# tRexRunnerNano.net
KiCad netlist of a schematic drawn in EAGLE
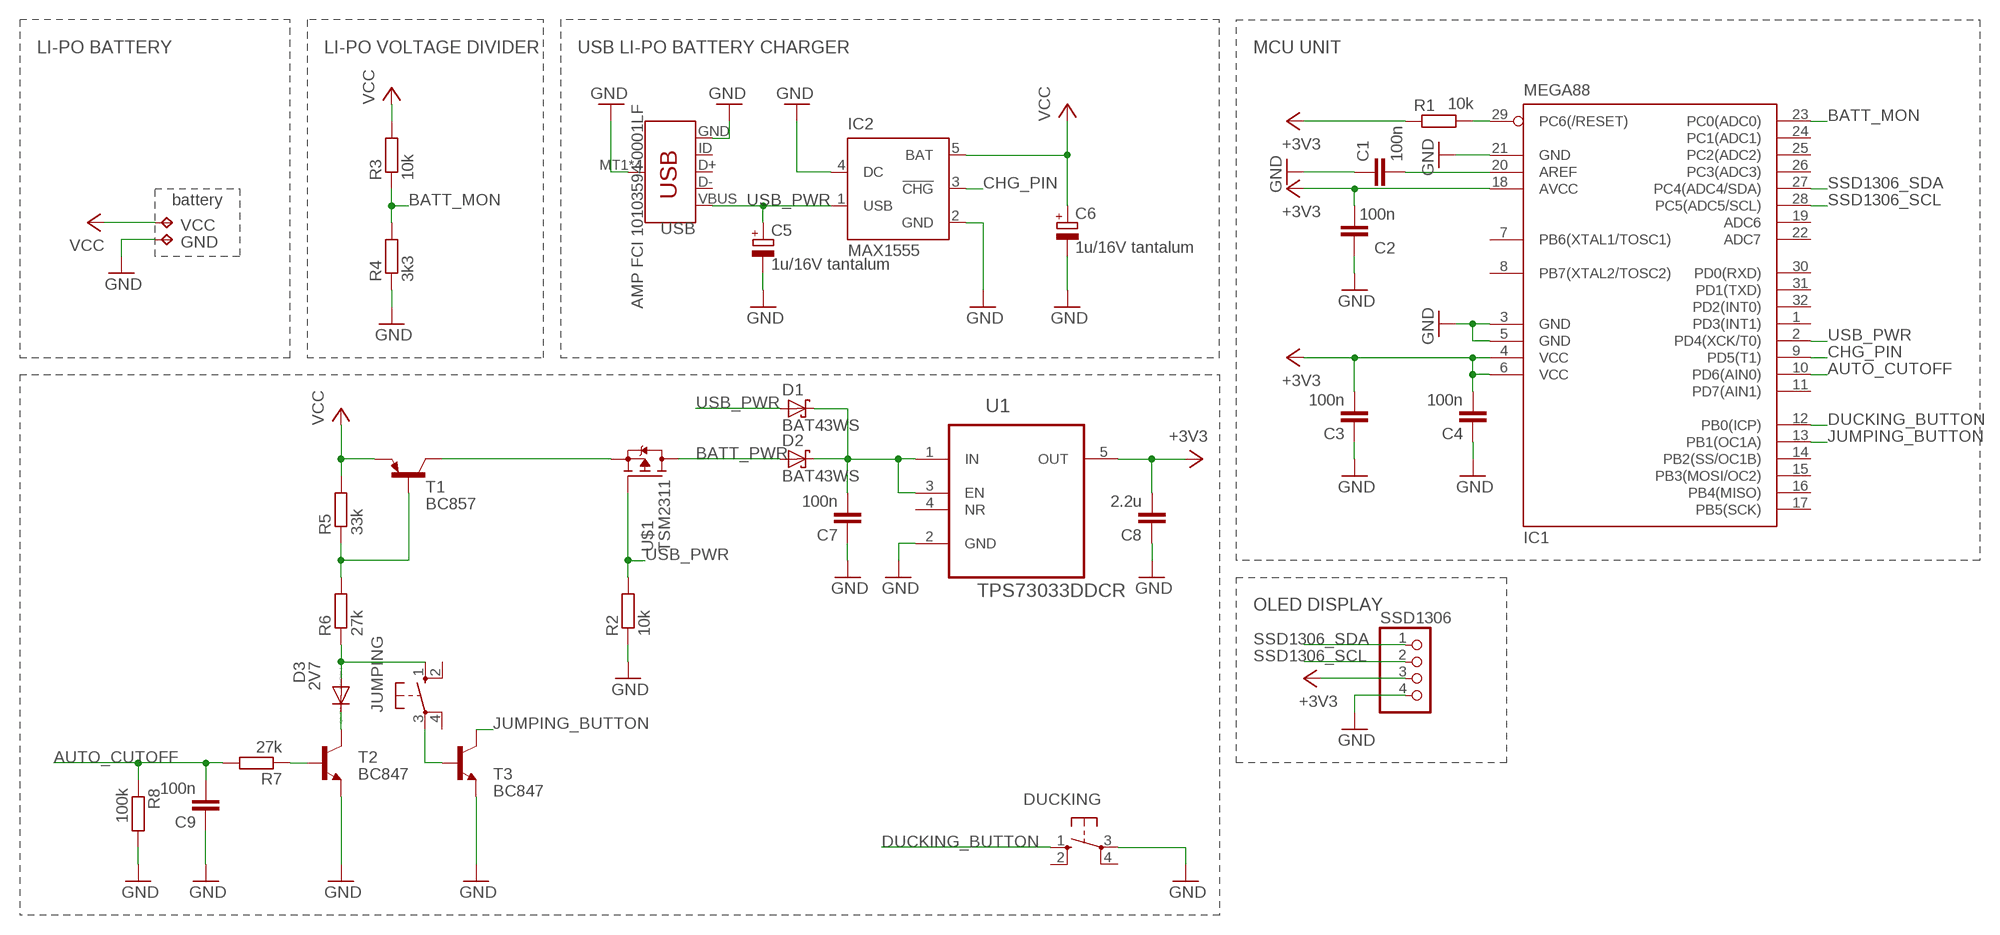
[diagram p0: schematic, sheet 1]

(export (version "E")
  (design (tool "Eeschema 10.0.6"))
  (components
    (comp (ref "C1")
      (value "100n")
      (footprint "eagle-import:C0805")
      (libsource (lib "eagle-import") (part "C-EUC0805"))
    )
    (comp (ref "C2")
      (value "100n")
      (footprint "eagle-import:C0805")
      (libsource (lib "eagle-import") (part "C-EUC0805"))
    )
    (comp (ref "C3")
      (value "100n")
      (footprint "eagle-import:C0805")
      (libsource (lib "eagle-import") (part "C-EUC0805"))
    )
    (comp (ref "C4")
      (value "100n")
      (footprint "eagle-import:C0805")
      (libsource (lib "eagle-import") (part "C-EUC0805"))
    )
    (comp (ref "C5")
      (value "1u/16V tantalum")
      (footprint "eagle-import:SMC_A")
      (libsource (lib "eagle-import") (part "CPOL-EUSMCA"))
    )
    (comp (ref "C6")
      (value "1u/16V tantalum")
      (footprint "eagle-import:SMC_A")
      (libsource (lib "eagle-import") (part "CPOL-EUSMCA"))
    )
    (comp (ref "C7")
      (value "100n")
      (footprint "eagle-import:C0805")
      (libsource (lib "eagle-import") (part "C-EUC0805"))
    )
    (comp (ref "C8")
      (value "2.2u")
      (footprint "eagle-import:C0805")
      (libsource (lib "eagle-import") (part "C-EUC0805"))
    )
    (comp (ref "C9")
      (value "100n")
      (footprint "eagle-import:C0805")
      (libsource (lib "eagle-import") (part "C-EUC0805"))
    )
    (comp (ref "D1")
      (value "BAT43WS")
      (footprint "eagle-import:SOD323_ST")
      (libsource (lib "eagle-import") (part "BAT60J"))
    )
    (comp (ref "D2")
      (value "BAT43WS")
      (footprint "eagle-import:SOD323_ST")
      (libsource (lib "eagle-import") (part "BAT60J"))
    )
    (comp (ref "D3")
      (value "2V7")
      (footprint "eagle-import:SOD80C")
      (libsource (lib "eagle-import") (part "DIODE-SOD80C"))
    )
    (comp (ref "DUCKING")
      (value "10-XX")
      (footprint "eagle-import:B3F-10XX")
      (fields (field (name "MPN") "B3F-1000"))
      (libsource (lib "eagle-import") (part "10-XX"))
    )
    (comp (ref "GND")
      (value "TPTP12R")
      (footprint "eagle-import:TP12R")
      (libsource (lib "eagle-import") (part "TPTP12R"))
    )
    (comp (ref "IC1")
      (value "MEGA88")
      (footprint "eagle-import:TQFP32-08")
      (fields (field (name "MPN") "ATMEGA8-16AU"))
      (libsource (lib "eagle-import") (part "MEGA8-AI"))
    )
    (comp (ref "IC2")
      (value "MAX1555")
      (footprint "eagle-import:SOT23-5L")
      (fields (field (name "MF") "MAXIM") (field (name "MPN") "MAX1555EZK+T"))
      (libsource (lib "eagle-import") (part "MAX1555"))
    )
    (comp (ref "JUMPING")
      (value "10-XX")
      (footprint "eagle-import:B3F-10XX")
      (fields (field (name "MPN") "B3F-1000"))
      (libsource (lib "eagle-import") (part "10-XX"))
    )
    (comp (ref "R1")
      (value "10k")
      (footprint "eagle-import:R0805")
      (libsource (lib "eagle-import") (part "R-EU_R0805"))
    )
    (comp (ref "R2")
      (value "10k")
      (footprint "eagle-import:R0805")
      (libsource (lib "eagle-import") (part "R-EU_R0805"))
    )
    (comp (ref "R3")
      (value "10k")
      (footprint "eagle-import:R0805")
      (libsource (lib "eagle-import") (part "R-EU_R0805"))
    )
    (comp (ref "R4")
      (value "3k3")
      (footprint "eagle-import:R0805")
      (libsource (lib "eagle-import") (part "R-EU_R0805"))
    )
    (comp (ref "R5")
      (value "33k")
      (footprint "eagle-import:R0805")
      (libsource (lib "eagle-import") (part "R-EU_R0805"))
    )
    (comp (ref "R6")
      (value "27k")
      (footprint "eagle-import:R0805")
      (libsource (lib "eagle-import") (part "R-EU_R0805"))
    )
    (comp (ref "R7")
      (value "27k")
      (footprint "eagle-import:R0805")
      (libsource (lib "eagle-import") (part "R-EU_R0805"))
    )
    (comp (ref "R8")
      (value "100k")
      (footprint "eagle-import:R0805")
      (libsource (lib "eagle-import") (part "R-EU_R0805"))
    )
    (comp (ref "SSD1306")
      (value "PINHD-1X4")
      (footprint "eagle-import:1X04")
      (libsource (lib "eagle-import") (part "PINHD-1X4"))
    )
    (comp (ref "T1")
      (value "BC857")
      (footprint "eagle-import:SOT23-BEC")
      (libsource (lib "eagle-import") (part "-PNP-SOT23-BECBC857A"))
    )
    (comp (ref "T2")
      (value "BC847")
      (footprint "eagle-import:SOT23")
      (libsource (lib "eagle-import") (part "BC847"))
    )
    (comp (ref "T3")
      (value "BC847")
      (footprint "eagle-import:SOT23")
      (libsource (lib "eagle-import") (part "BC847"))
    )
    (comp (ref "U$1")
      (value "TSM2311")
      (footprint "eagle-import:SOT23")
      (libsource (lib "eagle-import") (part "TSM2311"))
    )
    (comp (ref "U1")
      (value "TPS73033DDCR")
      (footprint "eagle-import:SOT95P290X145-5N")
      (fields (field (name "MPN") "TPS73033DBVT"))
      (libsource (lib "eagle-import") (part "TPS73033DBVT"))
    )
    (comp (ref "USB")
      (value "AMP FCI 10103594-0001LF")
      (footprint "eagle-import:USB-MICROB")
      (libsource (lib "eagle-import") (part "USB_MICRO-B_SMT"))
    )
    (comp (ref "VCC")
      (value "TPTP12R")
      (footprint "eagle-import:TP12R")
      (libsource (lib "eagle-import") (part "TPTP12R"))
    )
  )
  (nets
    (net (code "1") (name "+3V3") (class "Default")
      (node (ref "C2") (pin "2") (pinfunction "2_2") (pintype "passive"))
      (node (ref "C3") (pin "2") (pinfunction "2_2") (pintype "passive"))
      (node (ref "C4") (pin "2") (pinfunction "2_2") (pintype "passive"))
      (node (ref "C8") (pin "2") (pinfunction "2_2") (pintype "passive"))
      (node (ref "IC1") (pin "18") (pinfunction "AVCC_18") (pintype "power_in"))
      (node (ref "IC1") (pin "4") (pinfunction "VCC_4") (pintype "power_in"))
      (node (ref "IC1") (pin "6") (pinfunction "VCC_6") (pintype "power_in"))
      (node (ref "R1") (pin "1") (pinfunction "1_1") (pintype "passive"))
      (node (ref "SSD1306") (pin "3") (pinfunction "3_3") (pintype "passive"))
      (node (ref "U1") (pin "5") (pinfunction "OUT_5") (pintype "output"))
    )
    (net (code "2") (name "/AUTO_CUTOFF") (class "Default")
      (node (ref "C9") (pin "2") (pinfunction "2_2") (pintype "passive"))
      (node (ref "IC1") (pin "10") (pinfunction "PD6(AIN0)_10") (pintype "bidirectional"))
      (node (ref "R7") (pin "2") (pinfunction "2_2") (pintype "passive"))
      (node (ref "R8") (pin "1") (pinfunction "1_1") (pintype "passive"))
    )
    (net (code "3") (name "/BATT_MON") (class "Default")
      (node (ref "IC1") (pin "23") (pinfunction "PC0(ADC0)_23") (pintype "bidirectional"))
      (node (ref "R3") (pin "1") (pinfunction "1_1") (pintype "passive"))
      (node (ref "R4") (pin "2") (pinfunction "2_2") (pintype "passive"))
    )
    (net (code "4") (name "/BATT_PWR") (class "Default")
      (node (ref "D2") (pin "A") (pinfunction "A_A") (pintype "passive"))
      (node (ref "U$1") (pin "3") (pinfunction "D_3") (pintype "passive"))
    )
    (net (code "5") (name "/CHG_PIN") (class "Default")
      (node (ref "IC1") (pin "9") (pinfunction "PD5(T1)_9") (pintype "bidirectional"))
      (node (ref "IC2") (pin "3") (pinfunction "~{CHG}_3") (pintype "output"))
    )
    (net (code "6") (name "/DUCKING_BUTTON") (class "Default")
      (node (ref "DUCKING") (pin "1") (pinfunction "S_1") (pintype "passive"))
      (node (ref "IC1") (pin "12") (pinfunction "PB0(ICP)_12") (pintype "bidirectional"))
    )
    (net (code "7") (name "/JUMPING_BUTTON") (class "Default")
      (node (ref "IC1") (pin "13") (pinfunction "PB1(OC1A)_13") (pintype "bidirectional"))
      (node (ref "T3") (pin "3") (pinfunction "C_3") (pintype "passive"))
    )
    (net (code "8") (name "/SSD1306_SCL") (class "Default")
      (node (ref "IC1") (pin "28") (pinfunction "PC5(ADC5/SCL)_28") (pintype "bidirectional"))
      (node (ref "SSD1306") (pin "2") (pinfunction "2_2") (pintype "passive"))
    )
    (net (code "9") (name "/SSD1306_SDA") (class "Default")
      (node (ref "IC1") (pin "27") (pinfunction "PC4(ADC4/SDA)_27") (pintype "bidirectional"))
      (node (ref "SSD1306") (pin "1") (pinfunction "1_1") (pintype "passive"))
    )
    (net (code "10") (name "/USB_PWR") (class "Default")
      (node (ref "C5") (pin "+") (pinfunction "+_+") (pintype "passive"))
      (node (ref "D1") (pin "A") (pinfunction "A_A") (pintype "passive"))
      (node (ref "IC1") (pin "2") (pinfunction "PD4(XCK/T0)_2") (pintype "bidirectional"))
      (node (ref "IC2") (pin "1") (pinfunction "USB_1") (pintype "input"))
      (node (ref "R2") (pin "2") (pinfunction "2_2") (pintype "passive"))
      (node (ref "U$1") (pin "1") (pinfunction "G_1") (pintype "passive"))
      (node (ref "USB") (pin "VBUS") (pinfunction "VBUS_VBUS") (pintype "power_in"))
    )
    (net (code "11") (name "GND") (class "Default")
      (node (ref "C1") (pin "1") (pinfunction "1_1") (pintype "passive"))
      (node (ref "C2") (pin "1") (pinfunction "1_1") (pintype "passive"))
      (node (ref "C3") (pin "1") (pinfunction "1_1") (pintype "passive"))
      (node (ref "C4") (pin "1") (pinfunction "1_1") (pintype "passive"))
      (node (ref "C5") (pin "-") (pinfunction "-_-") (pintype "passive"))
      (node (ref "C6") (pin "-") (pinfunction "-_-") (pintype "passive"))
      (node (ref "C7") (pin "1") (pinfunction "1_1") (pintype "passive"))
      (node (ref "C8") (pin "1") (pinfunction "1_1") (pintype "passive"))
      (node (ref "C9") (pin "1") (pinfunction "1_1") (pintype "passive"))
      (node (ref "DUCKING") (pin "3") (pinfunction "P_3") (pintype "passive"))
      (node (ref "GND") (pin "TP") (pinfunction "TP_TP") (pintype "input"))
      (node (ref "IC1") (pin "21") (pinfunction "GND_21") (pintype "power_in"))
      (node (ref "IC1") (pin "3") (pinfunction "GND_3") (pintype "power_in"))
      (node (ref "IC1") (pin "5") (pinfunction "GND_5") (pintype "power_in"))
      (node (ref "IC2") (pin "2") (pinfunction "GND_2") (pintype "power_in"))
      (node (ref "IC2") (pin "4") (pinfunction "DC_4") (pintype "input"))
      (node (ref "R2") (pin "1") (pinfunction "1_1") (pintype "passive"))
      (node (ref "R4") (pin "1") (pinfunction "1_1") (pintype "passive"))
      (node (ref "R8") (pin "2") (pinfunction "2_2") (pintype "passive"))
      (node (ref "SSD1306") (pin "4") (pinfunction "4_4") (pintype "passive"))
      (node (ref "T2") (pin "2") (pinfunction "E_2") (pintype "passive"))
      (node (ref "T3") (pin "2") (pinfunction "E_2") (pintype "passive"))
      (node (ref "U1") (pin "2") (pinfunction "GND_2") (pintype "passive"))
      (node (ref "USB") (pin "GND") (pinfunction "GND_GND") (pintype "power_in"))
      (node (ref "USB") (pin "MT1") (pinfunction "SHIELD_MT1") (pintype "bidirectional"))
      (node (ref "USB") (pin "MT2") (pinfunction "SHIELD_MT2") (pintype "bidirectional"))
      (node (ref "USB") (pin "P$1") (pinfunction "SHIELD_P$1") (pintype "bidirectional"))
      (node (ref "USB") (pin "P$2") (pinfunction "SHIELD_P$2") (pintype "bidirectional"))
    )
    (net (code "12") (name "Net-(IC1-AREF)") (class "Default")
      (node (ref "C1") (pin "2") (pinfunction "2_2") (pintype "passive"))
      (node (ref "IC1") (pin "20") (pinfunction "AREF_20") (pintype "passive"))
    )
    (net (code "13") (name "Net-(IC1-PC6({slash}RESET))") (class "Default")
      (node (ref "IC1") (pin "29") (pinfunction "PC6(/RESET)_29") (pintype "bidirectional"))
      (node (ref "R1") (pin "2") (pinfunction "2_2") (pintype "passive"))
    )
    (net (code "14") (name "Net-(JUMPING-P)") (class "Default")
      (node (ref "JUMPING") (pin "3") (pinfunction "P_3") (pintype "passive"))
      (node (ref "T3") (pin "1") (pinfunction "B_1") (pintype "passive"))
    )
    (net (code "15") (name "Net-(JUMPING-S)") (class "Default")
      (node (ref "D3") (pin "A") (pinfunction "A_A") (pintype "passive"))
      (node (ref "JUMPING") (pin "1") (pinfunction "S_1") (pintype "passive"))
      (node (ref "R6") (pin "1") (pinfunction "1_1") (pintype "passive"))
    )
    (net (code "16") (name "Net-(R5-Pad1)") (class "Default")
      (node (ref "R5") (pin "1") (pinfunction "1_1") (pintype "passive"))
      (node (ref "R6") (pin "2") (pinfunction "2_2") (pintype "passive"))
      (node (ref "T1") (pin "B") (pinfunction "B_B") (pintype "passive"))
    )
    (net (code "17") (name "Net-(T2-B)") (class "Default")
      (node (ref "R7") (pin "1") (pinfunction "1_1") (pintype "passive"))
      (node (ref "T2") (pin "1") (pinfunction "B_1") (pintype "passive"))
    )
    (net (code "18") (name "Net-(T2-C)") (class "Default")
      (node (ref "D3") (pin "C") (pinfunction "C_C") (pintype "passive"))
      (node (ref "T2") (pin "3") (pinfunction "C_3") (pintype "passive"))
    )
    (net (code "19") (name "Net-(U$1-S)") (class "Default")
      (node (ref "T1") (pin "C") (pinfunction "C_C") (pintype "passive"))
      (node (ref "U$1") (pin "2") (pinfunction "S_2") (pintype "passive"))
    )
    (net (code "20") (name "Net-(U1-EN)") (class "Default")
      (node (ref "C7") (pin "2") (pinfunction "2_2") (pintype "passive"))
      (node (ref "D1") (pin "C") (pinfunction "C_C") (pintype "passive"))
      (node (ref "D2") (pin "C") (pinfunction "C_C") (pintype "passive"))
      (node (ref "U1") (pin "1") (pinfunction "IN_1") (pintype "input"))
      (node (ref "U1") (pin "3") (pinfunction "EN_3") (pintype "input"))
    )
    (net (code "21") (name "VCC") (class "Default")
      (node (ref "C6") (pin "+") (pinfunction "+_+") (pintype "passive"))
      (node (ref "IC2") (pin "5") (pinfunction "BAT_5") (pintype "passive"))
      (node (ref "R3") (pin "2") (pinfunction "2_2") (pintype "passive"))
      (node (ref "R5") (pin "2") (pinfunction "2_2") (pintype "passive"))
      (node (ref "T1") (pin "E") (pinfunction "E_E") (pintype "passive"))
      (node (ref "VCC") (pin "TP") (pinfunction "TP_TP") (pintype "input"))
    )
    (net (code "22") (name "unconnected-(DUCKING-P1-Pad4)") (class "Default")
      (node (ref "DUCKING") (pin "4") (pinfunction "P1_4") (pintype "passive"))
    )
    (net (code "23") (name "unconnected-(DUCKING-S1-Pad2)") (class "Default")
      (node (ref "DUCKING") (pin "2") (pinfunction "S1_2") (pintype "passive"))
    )
    (net (code "24") (name "unconnected-(IC1-ADC6-Pad19)") (class "Default")
      (node (ref "IC1") (pin "19") (pinfunction "ADC6_19") (pintype "bidirectional"))
    )
    (net (code "25") (name "unconnected-(IC1-ADC7-Pad22)") (class "Default")
      (node (ref "IC1") (pin "22") (pinfunction "ADC7_22") (pintype "bidirectional"))
    )
    (net (code "26") (name "unconnected-(IC1-PB2(SS{slash}OC1B)-Pad14)") (class "Default")
      (node (ref "IC1") (pin "14") (pinfunction "PB2(SS/OC1B)_14") (pintype "bidirectional"))
    )
    (net (code "27") (name "unconnected-(IC1-PB3(MOSI{slash}OC2)-Pad15)") (class "Default")
      (node (ref "IC1") (pin "15") (pinfunction "PB3(MOSI/OC2)_15") (pintype "bidirectional"))
    )
    (net (code "28") (name "unconnected-(IC1-PB4(MISO)-Pad16)") (class "Default")
      (node (ref "IC1") (pin "16") (pinfunction "PB4(MISO)_16") (pintype "bidirectional"))
    )
    (net (code "29") (name "unconnected-(IC1-PB5(SCK)-Pad17)") (class "Default")
      (node (ref "IC1") (pin "17") (pinfunction "PB5(SCK)_17") (pintype "bidirectional"))
    )
    (net (code "30") (name "unconnected-(IC1-PB6(XTAL1{slash}TOSC1)-Pad7)") (class "Default")
      (node (ref "IC1") (pin "7") (pinfunction "PB6(XTAL1/TOSC1)_7") (pintype "bidirectional"))
    )
    (net (code "31") (name "unconnected-(IC1-PB7(XTAL2{slash}TOSC2)-Pad8)") (class "Default")
      (node (ref "IC1") (pin "8") (pinfunction "PB7(XTAL2/TOSC2)_8") (pintype "bidirectional"))
    )
    (net (code "32") (name "unconnected-(IC1-PC1(ADC1)-Pad24)") (class "Default")
      (node (ref "IC1") (pin "24") (pinfunction "PC1(ADC1)_24") (pintype "bidirectional"))
    )
    (net (code "33") (name "unconnected-(IC1-PC2(ADC2)-Pad25)") (class "Default")
      (node (ref "IC1") (pin "25") (pinfunction "PC2(ADC2)_25") (pintype "bidirectional"))
    )
    (net (code "34") (name "unconnected-(IC1-PC3(ADC3)-Pad26)") (class "Default")
      (node (ref "IC1") (pin "26") (pinfunction "PC3(ADC3)_26") (pintype "bidirectional"))
    )
    (net (code "35") (name "unconnected-(IC1-PD0(RXD)-Pad30)") (class "Default")
      (node (ref "IC1") (pin "30") (pinfunction "PD0(RXD)_30") (pintype "bidirectional"))
    )
    (net (code "36") (name "unconnected-(IC1-PD1(TXD)-Pad31)") (class "Default")
      (node (ref "IC1") (pin "31") (pinfunction "PD1(TXD)_31") (pintype "bidirectional"))
    )
    (net (code "37") (name "unconnected-(IC1-PD2(INT0)-Pad32)") (class "Default")
      (node (ref "IC1") (pin "32") (pinfunction "PD2(INT0)_32") (pintype "bidirectional"))
    )
    (net (code "38") (name "unconnected-(IC1-PD3(INT1)-Pad1)") (class "Default")
      (node (ref "IC1") (pin "1") (pinfunction "PD3(INT1)_1") (pintype "bidirectional"))
    )
    (net (code "39") (name "unconnected-(IC1-PD7(AIN1)-Pad11)") (class "Default")
      (node (ref "IC1") (pin "11") (pinfunction "PD7(AIN1)_11") (pintype "bidirectional"))
    )
    (net (code "40") (name "unconnected-(JUMPING-P1-Pad4)") (class "Default")
      (node (ref "JUMPING") (pin "4") (pinfunction "P1_4") (pintype "passive"))
    )
    (net (code "41") (name "unconnected-(JUMPING-S1-Pad2)") (class "Default")
      (node (ref "JUMPING") (pin "2") (pinfunction "S1_2") (pintype "passive"))
    )
    (net (code "42") (name "unconnected-(U1-NR-Pad4)") (class "Default")
      (node (ref "U1") (pin "4") (pinfunction "NR_4") (pintype "input"))
    )
    (net (code "43") (name "unconnected-(USB-PadD+)") (class "Default")
      (node (ref "USB") (pin "D+") (pinfunction "D+_D+") (pintype "bidirectional"))
    )
    (net (code "44") (name "unconnected-(USB-PadD-)") (class "Default")
      (node (ref "USB") (pin "D-") (pinfunction "D-_D-") (pintype "bidirectional"))
    )
    (net (code "45") (name "unconnected-(USB-PadID)") (class "Default")
      (node (ref "USB") (pin "ID") (pinfunction "ID_ID") (pintype "bidirectional"))
    )
  )
)
